# VFD_Clock.net
KiCad netlist of a schematic drawn in EasyEDA
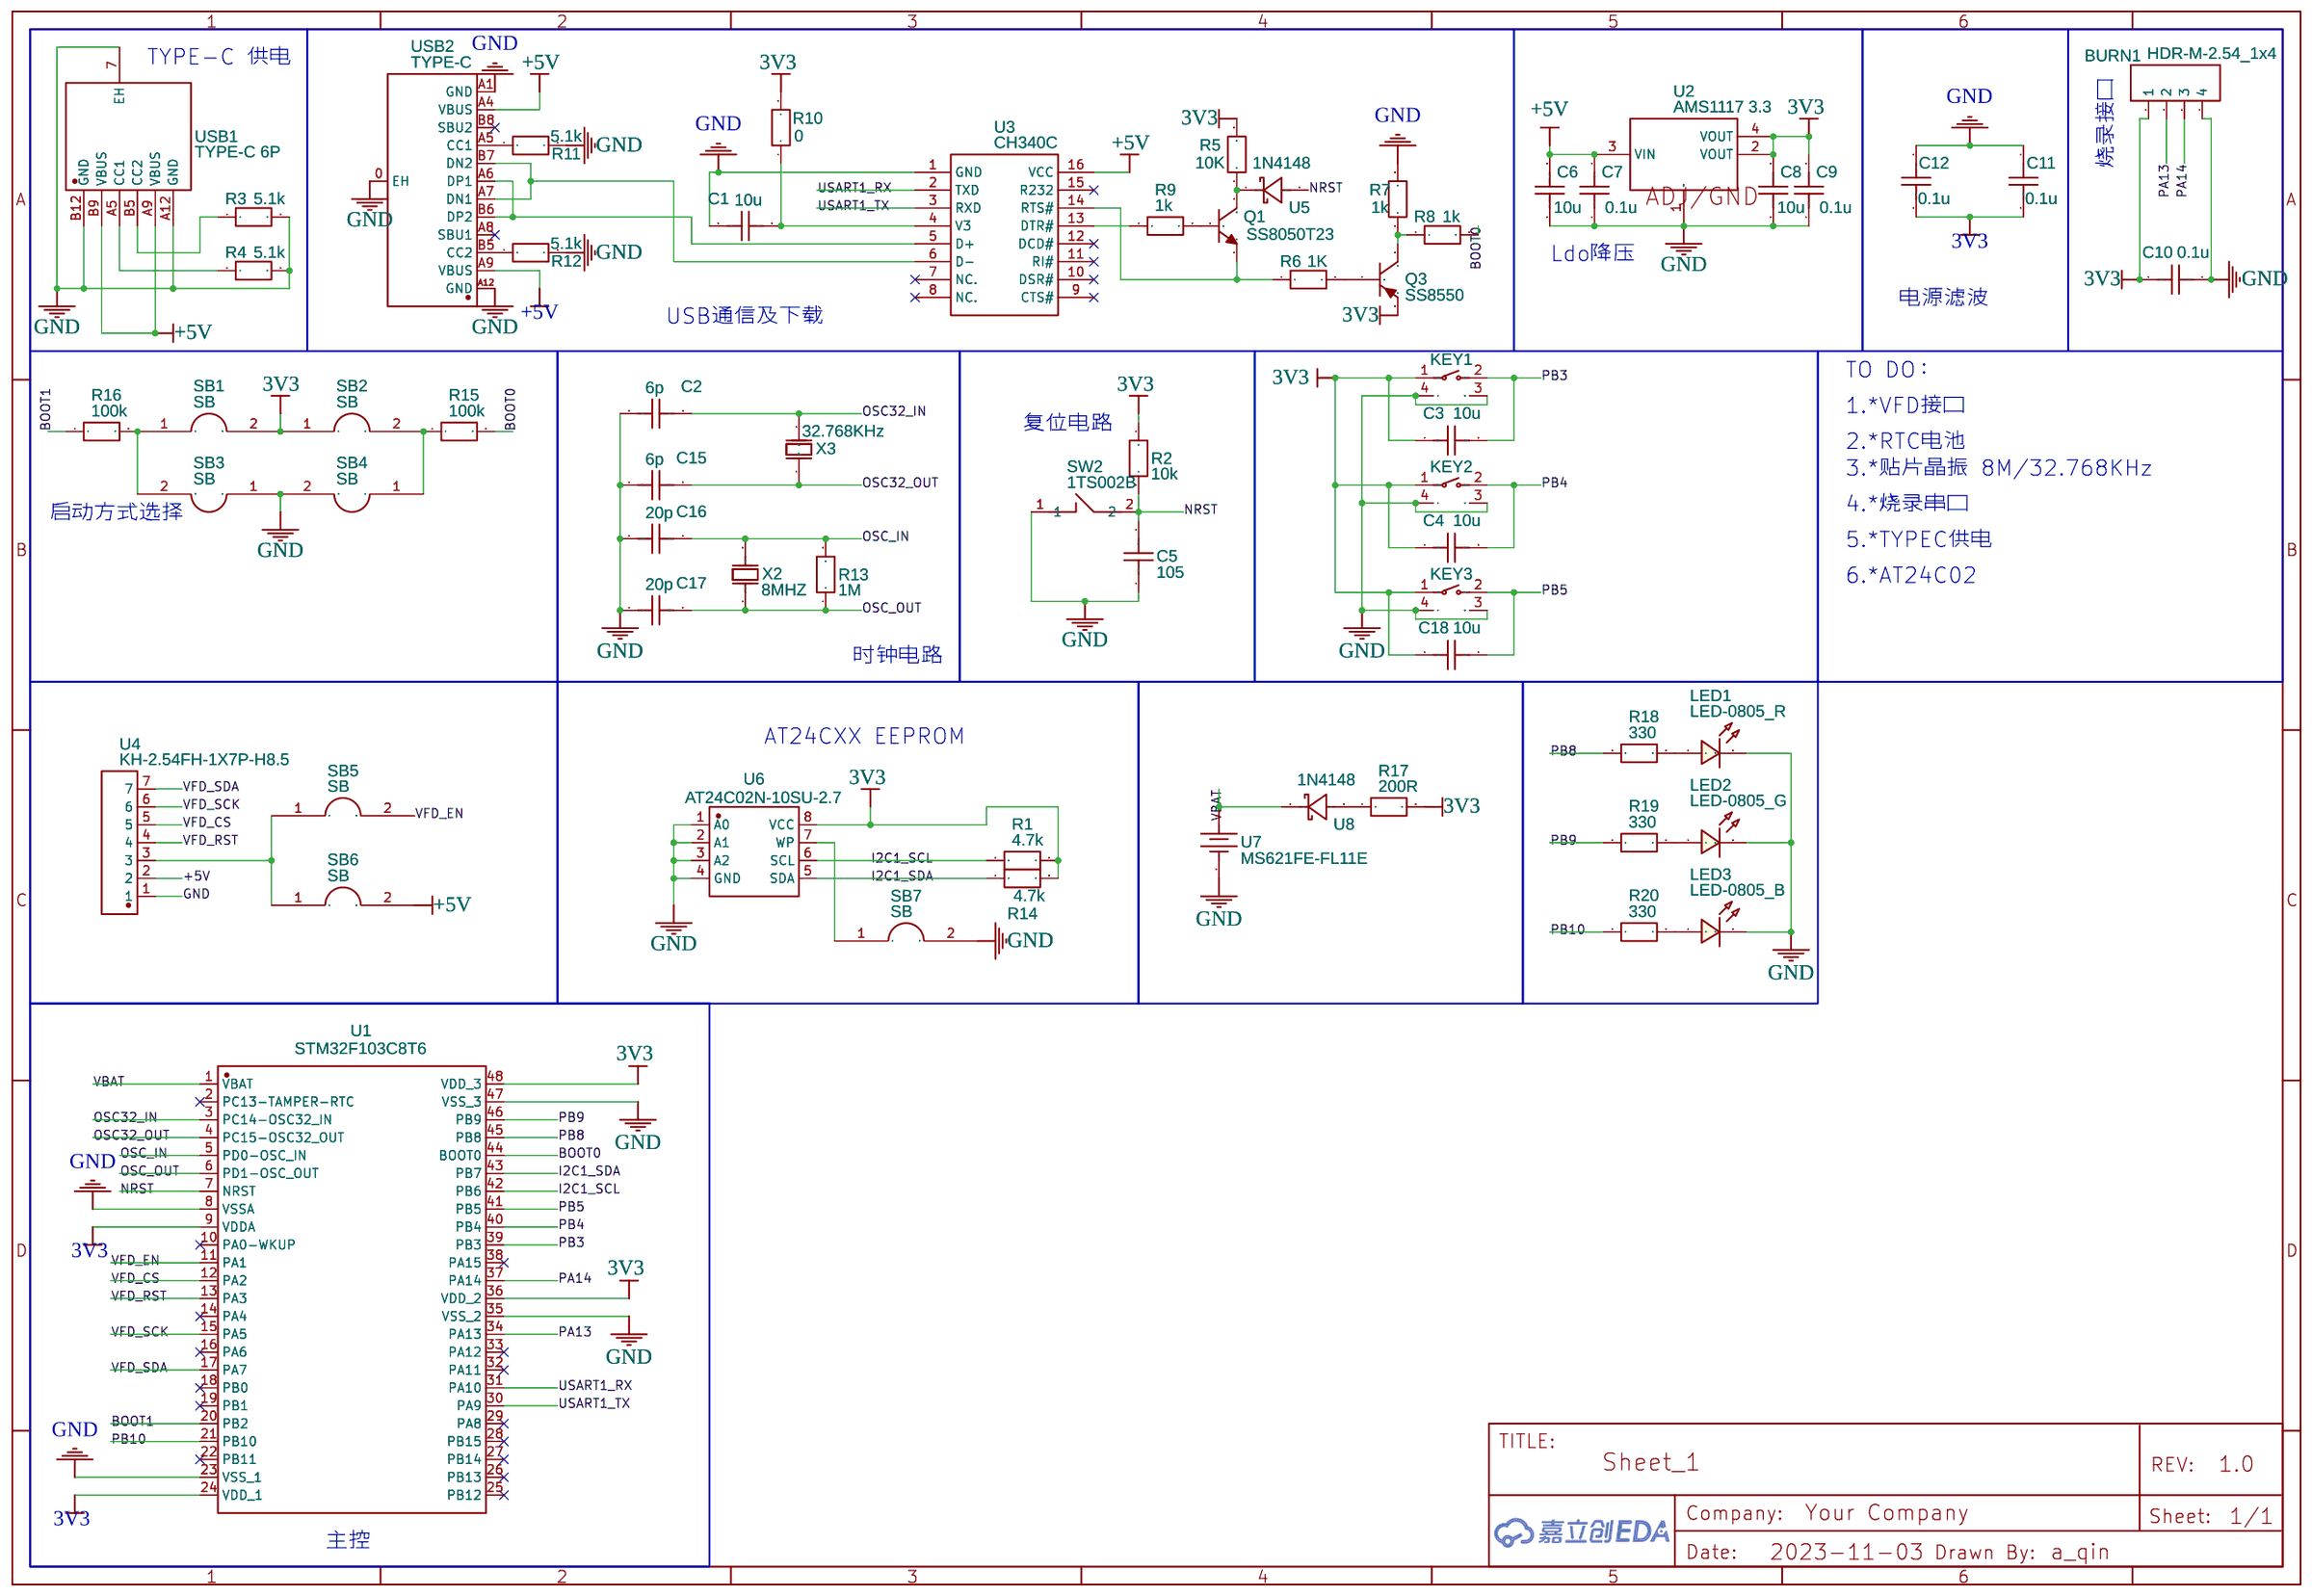
[diagram p0: schematic sheet]

(export (version "E")
  (design (tool "Eeschema 10.0.6"))
  (components
    (comp (ref "BURN1") (value "HDR-M-2.54_1x4") (libsource (lib "") (part "HDR-M-2.54_1x4")))
    (comp (ref "C1") (value "10u") (libsource (lib "") (part "C_0805_US")))
    (comp (ref "C2") (value "6p") (libsource (lib "") (part "C_0805_US")))
    (comp (ref "C3") (value "10u") (libsource (lib "") (part "C_0805_US")))
    (comp (ref "C4") (value "10u") (libsource (lib "") (part "C_0805_US")))
    (comp (ref "C5") (value "105") (libsource (lib "") (part "C_0805_US_3")))
    (comp (ref "C6") (value "10u") (libsource (lib "") (part "C_0805_US_3")))
    (comp (ref "C7") (value "0.1u") (libsource (lib "") (part "C_0805_US_3")))
    (comp (ref "C8") (value "10u") (libsource (lib "") (part "C_0805_US_3")))
    (comp (ref "C9") (value "0.1u") (libsource (lib "") (part "C_0805_US_3")))
    (comp (ref "C10") (value "0.1u") (libsource (lib "") (part "C_0805_US_2")))
    (comp (ref "C11") (value "0.1u") (libsource (lib "") (part "C_0805_US_1")))
    (comp (ref "C12") (value "0.1u") (libsource (lib "") (part "C_0805_US_1")))
    (comp (ref "C15") (value "6p") (libsource (lib "") (part "C_0805_US")))
    (comp (ref "C16") (value "20p") (libsource (lib "") (part "C_0805_US")))
    (comp (ref "C17") (value "20p") (libsource (lib "") (part "C_0805_US")))
    (comp (ref "C18") (value "10u") (libsource (lib "") (part "C_0805_US")))
    (comp (ref "KEY1")
      (value "K2-1102AQ-C4CW-01")
      (fields (field (name "Manufacturer") "韩国韩荣"))
      (libsource (lib "") (part "K2-1102AQ-C4CW-01"))
    )
    (comp (ref "KEY2")
      (value "K2-1102AQ-C4CW-01")
      (fields (field (name "Manufacturer") "韩国韩荣"))
      (libsource (lib "") (part "K2-1102AQ-C4CW-01"))
    )
    (comp (ref "KEY3")
      (value "K2-1102AQ-C4CW-01")
      (fields (field (name "Manufacturer") "韩国韩荣"))
      (libsource (lib "") (part "K2-1102AQ-C4CW-01"))
    )
    (comp (ref "LED1")
      (value "LED-0805_R")
      (fields
        (field (name "Manufacturer Part") "17-21SURC/S530-A3/TR8")
        (field (name "Manufacturer") "EVERLIGHT(台湾亿光)")
      )
      (libsource (lib "") (part "LED-0805_R"))
    )
    (comp (ref "LED2")
      (value "LED-0805_G")
      (fields (field (name "Manufacturer Part") "NCD0805G1") (field (name "Manufacturer") "国星光电"))
      (libsource (lib "") (part "LED-0805_G"))
    )
    (comp (ref "LED3")
      (value "LED-0805_B")
      (fields (field (name "Manufacturer Part") "D-B080508B1-KS2") (field (name "Manufacturer") "方舟 ARKLED"))
      (libsource (lib "") (part "LED-0805_B"))
    )
    (comp (ref "Q1")
      (value "SS8050T23")
      (fields (field (name "Manufacturer") "Me-TECH(美台高科)"))
      (libsource (lib "") (part "SS8050T23"))
    )
    (comp (ref "Q3")
      (value "SS8550")
      (fields (field (name "Manufacturer") "Yenji"))
      (libsource (lib "") (part "SS8550-C148468"))
    )
    (comp (ref "R1") (value "4.7k") (libsource (lib "") (part "R_0805_EU")))
    (comp (ref "R2") (value "10k") (libsource (lib "") (part "R_0805_EU_1")))
    (comp (ref "R3") (value "5.1k") (libsource (lib "") (part "R_0805_EU")))
    (comp (ref "R4") (value "5.1k") (libsource (lib "") (part "R_0805_EU")))
    (comp (ref "R5") (value "10K") (libsource (lib "") (part "R_0805_EU_1")))
    (comp (ref "R6") (value "1K") (libsource (lib "") (part "R_0805_EU")))
    (comp (ref "R7") (value "1k") (libsource (lib "") (part "R_0805_EU_1")))
    (comp (ref "R8") (value "1k") (libsource (lib "") (part "R_0805_EU")))
    (comp (ref "R9") (value "1k") (libsource (lib "") (part "R_0805_EU")))
    (comp (ref "R10") (value "0") (libsource (lib "") (part "R_0805_EU_1")))
    (comp (ref "R11") (value "5.1k") (libsource (lib "") (part "R_0805_EU")))
    (comp (ref "R12") (value "5.1k") (libsource (lib "") (part "R_0805_EU")))
    (comp (ref "R13") (value "1M") (libsource (lib "") (part "R_0805_EU_1")))
    (comp (ref "R14") (value "4.7k") (libsource (lib "") (part "R_0805_EU")))
    (comp (ref "R15") (value "100k") (libsource (lib "") (part "R_0805_EU")))
    (comp (ref "R16") (value "100k") (libsource (lib "") (part "R_0805_EU")))
    (comp (ref "R17") (value "200R") (libsource (lib "") (part "R_0805_EU")))
    (comp (ref "R18") (value "330") (libsource (lib "") (part "R_0805_EU")))
    (comp (ref "R19") (value "330") (libsource (lib "") (part "R_0805_EU")))
    (comp (ref "R20") (value "330") (libsource (lib "") (part "R_0805_EU")))
    (comp (ref "SB1") (value "SB") (libsource (lib "") (part "SB_1")))
    (comp (ref "SB2") (value "SB") (libsource (lib "") (part "SB_1")))
    (comp (ref "SB3") (value "SB") (libsource (lib "") (part "SB")))
    (comp (ref "SB4") (value "SB") (libsource (lib "") (part "SB")))
    (comp (ref "SB5") (value "SB") (libsource (lib "") (part "SB_1")))
    (comp (ref "SB6") (value "SB") (libsource (lib "") (part "SB_1")))
    (comp (ref "SB7") (value "SB") (libsource (lib "") (part "SB_1")))
    (comp (ref "SW2")
      (value "1TS002B")
      (fields
        (field (name "Manufacturer Part") "1TS002B-2700-5001-CT")
        (field (name "Manufacturer") "HYP(鸿源精密)")
      )
      (libsource (lib "") (part "1TS002B-2700-5001"))
    )
    (comp (ref "U1")
      (value "STM32F103C8T6")
      (fields (field (name "Manufacturer") "ST(意法半导体)"))
      (libsource (lib "") (part "STM32F103C8T6"))
    )
    (comp (ref "U2")
      (value "AMS1117 3.3")
      (fields (field (name "Manufacturer Part") "LD1117ASTR") (field (name "Manufacturer") "ST(意法半导体)"))
      (libsource (lib "") (part "LD1117ASTR"))
    )
    (comp (ref "U3")
      (value "CH340C")
      (fields (field (name "Manufacturer") "WCH(南京沁恒)"))
      (libsource (lib "") (part "CH340C"))
    )
    (comp (ref "U4")
      (value "KH-2.54FH-1X7P-H8.5")
      (fields (field (name "Manufacturer") "kinghelm(金航标)"))
      (libsource (lib "") (part "KH-2.54FH-1X7P-H8.5"))
    )
    (comp (ref "U5")
      (value "1N4148")
      (fields (field (name "Manufacturer Part") "1N4148WS-HG3-08") (field (name "Manufacturer") "VISHAY(威世)"))
      (libsource (lib "") (part "1N4148WS-HG3-08"))
    )
    (comp (ref "U6") (value "AT24C02N-10SU-2.7") (libsource (lib "") (part "AT24C02N-10SU-2.7")))
    (comp (ref "U7")
      (value "MS621FE-FL11E")
      (fields (field (name "Manufacturer") "Seiko(精工)"))
      (libsource (lib "") (part "MS621FE-FL11E"))
    )
    (comp (ref "U8")
      (value "1N4148")
      (fields (field (name "Manufacturer Part") "1N4148WS-HG3-08") (field (name "Manufacturer") "VISHAY(威世)"))
      (libsource (lib "") (part "1N4148WS-HG3-08"))
    )
    (comp (ref "USB1")
      (value "TYPE-C 6P")
      (fields (field (name "Manufacturer") "SHOU HAN(首韩)"))
      (libsource (lib "") (part "TYPE-C 6P"))
    )
    (comp (ref "USB2")
      (value "TYPE-C")
      (fields
        (field (name "Manufacturer Part") "TYPE-C 16P QTWT")
        (field (name "Manufacturer") "SHOU HAN(首韩)")
      )
      (libsource (lib "") (part "TYPE-C 16P QTWT"))
    )
    (comp (ref "X2")
      (value "8MHZ")
      (fields (field (name "Manufacturer Part") "49SAC08000182060") (field (name "Manufacturer") "JGHC"))
      (libsource (lib "") (part "49SAC08000182060"))
    )
    (comp (ref "X3")
      (value "32.768KHz")
      (fields (field (name "Manufacturer Part") "CFS-20632768EZFB") (field (name "Manufacturer") "CITIZEN"))
      (libsource (lib "") (part "CFS-20632768EZFB"))
    )
  )
  (nets
    (net (code "1") (name "+5V") (class "Default")
      (node (ref "C6") (pin "2") (pinfunction "2_2") (pintype "unspecified"))
      (node (ref "C7") (pin "2") (pinfunction "2_2") (pintype "unspecified"))
      (node (ref "SB6") (pin "2") (pinfunction "2_2") (pintype "unspecified"))
      (node (ref "U2") (pin "3") (pinfunction "VIN_3") (pintype "passive"))
      (node (ref "U3") (pin "16") (pinfunction "VCC_16") (pintype "unspecified"))
      (node (ref "U4") (pin "2") (pinfunction "2_2") (pintype "unspecified"))
      (node (ref "USB1") (pin "A9") (pinfunction "VBUS_A9") (pintype "unspecified"))
      (node (ref "USB1") (pin "B9") (pinfunction "VBUS_B9") (pintype "unspecified"))
      (node (ref "USB2") (pin "A4") (pinfunction "VBUS_A4") (pintype "unspecified"))
      (node (ref "USB2") (pin "A9") (pinfunction "VBUS_A9") (pintype "unspecified"))
    )
    (net (code "2") (name "/BOOT0") (class "Default")
      (node (ref "R15") (pin "2") (pinfunction "2_2") (pintype "unspecified"))
      (node (ref "R8") (pin "2") (pinfunction "2_2") (pintype "unspecified"))
      (node (ref "U1") (pin "44") (pinfunction "BOOT0_44") (pintype "unspecified"))
    )
    (net (code "3") (name "/BOOT1") (class "Default")
      (node (ref "R16") (pin "1") (pinfunction "1_1") (pintype "unspecified"))
      (node (ref "U1") (pin "20") (pinfunction "PB2_20") (pintype "unspecified"))
    )
    (net (code "4") (name "/I2C1_SCL") (class "Default")
      (node (ref "R1") (pin "1") (pinfunction "1_1") (pintype "unspecified"))
      (node (ref "U1") (pin "42") (pinfunction "PB6_42") (pintype "unspecified"))
      (node (ref "U6") (pin "6") (pinfunction "SCL_6") (pintype "unspecified"))
    )
    (net (code "5") (name "/I2C1_SDA") (class "Default")
      (node (ref "R14") (pin "1") (pinfunction "1_1") (pintype "unspecified"))
      (node (ref "U1") (pin "43") (pinfunction "PB7_43") (pintype "unspecified"))
      (node (ref "U6") (pin "5") (pinfunction "SDA_5") (pintype "unspecified"))
    )
    (net (code "6") (name "/NRST") (class "Default")
      (node (ref "C5") (pin "2") (pinfunction "2_2") (pintype "unspecified"))
      (node (ref "R2") (pin "1") (pinfunction "1_1") (pintype "unspecified"))
      (node (ref "SW2") (pin "2") (pinfunction "2_2") (pintype "unspecified"))
      (node (ref "U1") (pin "7") (pinfunction "NRST_7") (pintype "unspecified"))
      (node (ref "U5") (pin "2") (pinfunction "A_2") (pintype "unspecified"))
    )
    (net (code "7") (name "/OSC32_IN") (class "Default")
      (node (ref "C2") (pin "2") (pinfunction "2_2") (pintype "unspecified"))
      (node (ref "U1") (pin "3") (pinfunction "PC14-OSC32_IN_3") (pintype "unspecified"))
      (node (ref "X3") (pin "2") (pinfunction "OSC2_2") (pintype "input"))
    )
    (net (code "8") (name "/OSC32_OUT") (class "Default")
      (node (ref "C15") (pin "2") (pinfunction "2_2") (pintype "unspecified"))
      (node (ref "U1") (pin "4") (pinfunction "PC15-OSC32_OUT_4") (pintype "unspecified"))
      (node (ref "X3") (pin "1") (pinfunction "OSC1_1") (pintype "input"))
    )
    (net (code "9") (name "/OSC_IN") (class "Default")
      (node (ref "C16") (pin "2") (pinfunction "2_2") (pintype "unspecified"))
      (node (ref "R13") (pin "2") (pinfunction "2_2") (pintype "unspecified"))
      (node (ref "U1") (pin "5") (pinfunction "PD0-OSC_IN_5") (pintype "unspecified"))
      (node (ref "X2") (pin "2") (pinfunction "OSC2_2") (pintype "input"))
    )
    (net (code "10") (name "/OSC_OUT") (class "Default")
      (node (ref "C17") (pin "2") (pinfunction "2_2") (pintype "unspecified"))
      (node (ref "R13") (pin "1") (pinfunction "1_1") (pintype "unspecified"))
      (node (ref "U1") (pin "6") (pinfunction "PD1-OSC_OUT_6") (pintype "unspecified"))
      (node (ref "X2") (pin "1") (pinfunction "OSC1_1") (pintype "input"))
    )
    (net (code "11") (name "/PA13") (class "Default")
      (node (ref "BURN1") (pin "2") (pinfunction "2_2") (pintype "unspecified"))
      (node (ref "U1") (pin "34") (pinfunction "PA13_34") (pintype "unspecified"))
    )
    (net (code "12") (name "/PA14") (class "Default")
      (node (ref "BURN1") (pin "3") (pinfunction "3_3") (pintype "unspecified"))
      (node (ref "U1") (pin "37") (pinfunction "PA14_37") (pintype "unspecified"))
    )
    (net (code "13") (name "/PB3") (class "Default")
      (node (ref "C3") (pin "2") (pinfunction "2_2") (pintype "unspecified"))
      (node (ref "KEY1") (pin "2") (pinfunction "2_2") (pintype "unspecified"))
      (node (ref "U1") (pin "39") (pinfunction "PB3_39") (pintype "unspecified"))
    )
    (net (code "14") (name "/PB4") (class "Default")
      (node (ref "C4") (pin "2") (pinfunction "2_2") (pintype "unspecified"))
      (node (ref "KEY2") (pin "2") (pinfunction "2_2") (pintype "unspecified"))
      (node (ref "U1") (pin "40") (pinfunction "PB4_40") (pintype "unspecified"))
    )
    (net (code "15") (name "/PB5") (class "Default")
      (node (ref "C18") (pin "2") (pinfunction "2_2") (pintype "unspecified"))
      (node (ref "KEY3") (pin "2") (pinfunction "2_2") (pintype "unspecified"))
      (node (ref "U1") (pin "41") (pinfunction "PB5_41") (pintype "unspecified"))
    )
    (net (code "16") (name "/PB8") (class "Default")
      (node (ref "R18") (pin "1") (pinfunction "1_1") (pintype "unspecified"))
      (node (ref "U1") (pin "45") (pinfunction "PB8_45") (pintype "unspecified"))
    )
    (net (code "17") (name "/PB9") (class "Default")
      (node (ref "R19") (pin "1") (pinfunction "1_1") (pintype "unspecified"))
      (node (ref "U1") (pin "46") (pinfunction "PB9_46") (pintype "unspecified"))
    )
    (net (code "18") (name "/PB10") (class "Default")
      (node (ref "R20") (pin "1") (pinfunction "1_1") (pintype "unspecified"))
      (node (ref "U1") (pin "21") (pinfunction "PB10_21") (pintype "unspecified"))
    )
    (net (code "19") (name "/USART1_RX") (class "Default")
      (node (ref "U1") (pin "31") (pinfunction "PA10_31") (pintype "unspecified"))
      (node (ref "U3") (pin "2") (pinfunction "TXD_2") (pintype "unspecified"))
    )
    (net (code "20") (name "/USART1_TX") (class "Default")
      (node (ref "U1") (pin "30") (pinfunction "PA9_30") (pintype "unspecified"))
      (node (ref "U3") (pin "3") (pinfunction "RXD_3") (pintype "unspecified"))
    )
    (net (code "21") (name "/VBAT") (class "Default")
      (node (ref "U1") (pin "1") (pinfunction "VBAT_1") (pintype "unspecified"))
      (node (ref "U7") (pin "1") (pinfunction "+_1") (pintype "passive"))
      (node (ref "U8") (pin "1") (pinfunction "K_1") (pintype "unspecified"))
    )
    (net (code "22") (name "/VFD_CS") (class "Default")
      (node (ref "U1") (pin "12") (pinfunction "PA2_12") (pintype "unspecified"))
      (node (ref "U4") (pin "5") (pinfunction "5_5") (pintype "unspecified"))
    )
    (net (code "23") (name "/VFD_EN") (class "Default")
      (node (ref "SB5") (pin "2") (pinfunction "2_2") (pintype "unspecified"))
      (node (ref "U1") (pin "11") (pinfunction "PA1_11") (pintype "unspecified"))
    )
    (net (code "24") (name "/VFD_RST") (class "Default")
      (node (ref "U1") (pin "13") (pinfunction "PA3_13") (pintype "unspecified"))
      (node (ref "U4") (pin "4") (pinfunction "4_4") (pintype "unspecified"))
    )
    (net (code "25") (name "/VFD_SCK") (class "Default")
      (node (ref "U1") (pin "15") (pinfunction "PA5_15") (pintype "unspecified"))
      (node (ref "U4") (pin "6") (pinfunction "6_6") (pintype "unspecified"))
    )
    (net (code "26") (name "/VFD_SDA") (class "Default")
      (node (ref "U1") (pin "17") (pinfunction "PA7_17") (pintype "unspecified"))
      (node (ref "U4") (pin "7") (pinfunction "7_7") (pintype "unspecified"))
    )
    (net (code "27") (name "3V3") (class "Default")
      (node (ref "BURN1") (pin "1") (pinfunction "1_1") (pintype "unspecified"))
      (node (ref "C10") (pin "2") (pinfunction "2_2") (pintype "unspecified"))
      (node (ref "C11") (pin "2") (pinfunction "2_2") (pintype "unspecified"))
      (node (ref "C12") (pin "2") (pinfunction "2_2") (pintype "unspecified"))
      (node (ref "C18") (pin "1") (pinfunction "1_1") (pintype "unspecified"))
      (node (ref "C3") (pin "1") (pinfunction "1_1") (pintype "unspecified"))
      (node (ref "C4") (pin "1") (pinfunction "1_1") (pintype "unspecified"))
      (node (ref "C8") (pin "2") (pinfunction "2_2") (pintype "unspecified"))
      (node (ref "C9") (pin "2") (pinfunction "2_2") (pintype "unspecified"))
      (node (ref "KEY1") (pin "1") (pinfunction "1_1") (pintype "unspecified"))
      (node (ref "KEY2") (pin "1") (pinfunction "1_1") (pintype "unspecified"))
      (node (ref "KEY3") (pin "1") (pinfunction "1_1") (pintype "unspecified"))
      (node (ref "Q3") (pin "2") (pinfunction "E_2") (pintype "unspecified"))
      (node (ref "R1") (pin "2") (pinfunction "2_2") (pintype "unspecified"))
      (node (ref "R10") (pin "2") (pinfunction "2_2") (pintype "unspecified"))
      (node (ref "R14") (pin "2") (pinfunction "2_2") (pintype "unspecified"))
      (node (ref "R17") (pin "2") (pinfunction "2_2") (pintype "unspecified"))
      (node (ref "R2") (pin "2") (pinfunction "2_2") (pintype "unspecified"))
      (node (ref "R5") (pin "2") (pinfunction "2_2") (pintype "unspecified"))
      (node (ref "SB1") (pin "2") (pinfunction "2_2") (pintype "unspecified"))
      (node (ref "SB2") (pin "1") (pinfunction "1_1") (pintype "unspecified"))
      (node (ref "U1") (pin "24") (pinfunction "VDD_1_24") (pintype "unspecified"))
      (node (ref "U1") (pin "36") (pinfunction "VDD_2_36") (pintype "unspecified"))
      (node (ref "U1") (pin "48") (pinfunction "VDD_3_48") (pintype "unspecified"))
      (node (ref "U1") (pin "9") (pinfunction "VDDA_9") (pintype "unspecified"))
      (node (ref "U2") (pin "2") (pinfunction "VOUT_2") (pintype "passive"))
      (node (ref "U2") (pin "4") (pinfunction "VOUT_4") (pintype "passive"))
      (node (ref "U6") (pin "8") (pinfunction "VCC_8") (pintype "unspecified"))
    )
    (net (code "28") (name "GND") (class "Default")
      (node (ref "BURN1") (pin "4") (pinfunction "4_4") (pintype "unspecified"))
      (node (ref "C1") (pin "1") (pinfunction "1_1") (pintype "unspecified"))
      (node (ref "C10") (pin "1") (pinfunction "1_1") (pintype "unspecified"))
      (node (ref "C11") (pin "1") (pinfunction "1_1") (pintype "unspecified"))
      (node (ref "C12") (pin "1") (pinfunction "1_1") (pintype "unspecified"))
      (node (ref "C15") (pin "1") (pinfunction "1_1") (pintype "unspecified"))
      (node (ref "C16") (pin "1") (pinfunction "1_1") (pintype "unspecified"))
      (node (ref "C17") (pin "1") (pinfunction "1_1") (pintype "unspecified"))
      (node (ref "C2") (pin "1") (pinfunction "1_1") (pintype "unspecified"))
      (node (ref "C5") (pin "1") (pinfunction "1_1") (pintype "unspecified"))
      (node (ref "C6") (pin "1") (pinfunction "1_1") (pintype "unspecified"))
      (node (ref "C7") (pin "1") (pinfunction "1_1") (pintype "unspecified"))
      (node (ref "C8") (pin "1") (pinfunction "1_1") (pintype "unspecified"))
      (node (ref "C9") (pin "1") (pinfunction "1_1") (pintype "unspecified"))
      (node (ref "KEY1") (pin "3") (pinfunction "3_3") (pintype "unspecified"))
      (node (ref "KEY1") (pin "4") (pinfunction "4_4") (pintype "unspecified"))
      (node (ref "KEY2") (pin "3") (pinfunction "3_3") (pintype "unspecified"))
      (node (ref "KEY2") (pin "4") (pinfunction "4_4") (pintype "unspecified"))
      (node (ref "KEY3") (pin "3") (pinfunction "3_3") (pintype "unspecified"))
      (node (ref "KEY3") (pin "4") (pinfunction "4_4") (pintype "unspecified"))
      (node (ref "LED1") (pin "2") (pinfunction "2_2") (pintype "unspecified"))
      (node (ref "LED2") (pin "2") (pinfunction "2_2") (pintype "unspecified"))
      (node (ref "LED3") (pin "2") (pinfunction "2_2") (pintype "unspecified"))
      (node (ref "R11") (pin "2") (pinfunction "2_2") (pintype "unspecified"))
      (node (ref "R12") (pin "2") (pinfunction "2_2") (pintype "unspecified"))
      (node (ref "R3") (pin "2") (pinfunction "2_2") (pintype "unspecified"))
      (node (ref "R4") (pin "2") (pinfunction "2_2") (pintype "unspecified"))
      (node (ref "R7") (pin "2") (pinfunction "2_2") (pintype "unspecified"))
      (node (ref "SB3") (pin "1") (pinfunction "1_1") (pintype "unspecified"))
      (node (ref "SB4") (pin "2") (pinfunction "2_2") (pintype "unspecified"))
      (node (ref "SB7") (pin "2") (pinfunction "2_2") (pintype "unspecified"))
      (node (ref "SW2") (pin "1") (pinfunction "1_1") (pintype "unspecified"))
      (node (ref "U1") (pin "23") (pinfunction "VSS_1_23") (pintype "unspecified"))
      (node (ref "U1") (pin "35") (pinfunction "VSS_2_35") (pintype "unspecified"))
      (node (ref "U1") (pin "47") (pinfunction "VSS_3_47") (pintype "unspecified"))
      (node (ref "U1") (pin "8") (pinfunction "VSSA_8") (pintype "unspecified"))
      (node (ref "U2") (pin "1") (pinfunction "ADJ/GND_1") (pintype "passive"))
      (node (ref "U3") (pin "1") (pinfunction "GND_1") (pintype "unspecified"))
      (node (ref "U4") (pin "1") (pinfunction "1_1") (pintype "unspecified"))
      (node (ref "U6") (pin "1") (pinfunction "A0_1") (pintype "unspecified"))
      (node (ref "U6") (pin "2") (pinfunction "A1_2") (pintype "unspecified"))
      (node (ref "U6") (pin "3") (pinfunction "A2_3") (pintype "unspecified"))
      (node (ref "U6") (pin "4") (pinfunction "GND_4") (pintype "unspecified"))
      (node (ref "U7") (pin "2") (pinfunction "-_2") (pintype "passive"))
      (node (ref "USB1") (pin "7") (pinfunction "EH_7") (pintype "unspecified"))
      (node (ref "USB1") (pin "A12") (pinfunction "GND_A12") (pintype "unspecified"))
      (node (ref "USB1") (pin "B12") (pinfunction "GND_B12") (pintype "unspecified"))
      (node (ref "USB2") (pin "0") (pinfunction "EH_0") (pintype "unspecified"))
      (node (ref "USB2") (pin "A1") (pinfunction "GND_A1") (pintype "unspecified"))
      (node (ref "USB2") (pin "A12") (pinfunction "GND_A12") (pintype "unspecified"))
    )
    (net (code "29") (name "Net-(LED1-Pad1)") (class "Default")
      (node (ref "LED1") (pin "1") (pinfunction "1_1") (pintype "unspecified"))
      (node (ref "R18") (pin "2") (pinfunction "2_2") (pintype "unspecified"))
    )
    (net (code "30") (name "Net-(LED2-Pad1)") (class "Default")
      (node (ref "LED2") (pin "1") (pinfunction "1_1") (pintype "unspecified"))
      (node (ref "R19") (pin "2") (pinfunction "2_2") (pintype "unspecified"))
    )
    (net (code "31") (name "Net-(LED3-Pad1)") (class "Default")
      (node (ref "LED3") (pin "1") (pinfunction "1_1") (pintype "unspecified"))
      (node (ref "R20") (pin "2") (pinfunction "2_2") (pintype "unspecified"))
    )
    (net (code "32") (name "Net-(Q1-B)") (class "Default")
      (node (ref "Q1") (pin "1") (pinfunction "B_1") (pintype "input"))
      (node (ref "R9") (pin "2") (pinfunction "2_2") (pintype "unspecified"))
    )
    (net (code "33") (name "Net-(Q1-C)") (class "Default")
      (node (ref "Q1") (pin "3") (pinfunction "C_3") (pintype "input"))
      (node (ref "R5") (pin "1") (pinfunction "1_1") (pintype "unspecified"))
      (node (ref "U5") (pin "1") (pinfunction "K_1") (pintype "unspecified"))
    )
    (net (code "34") (name "Net-(Q1-E)") (class "Default")
      (node (ref "Q1") (pin "2") (pinfunction "E_2") (pintype "input"))
      (node (ref "R6") (pin "1") (pinfunction "1_1") (pintype "unspecified"))
      (node (ref "U3") (pin "14") (pinfunction "RTS#_14") (pintype "unspecified"))
    )
    (net (code "35") (name "Net-(Q3-B)") (class "Default")
      (node (ref "Q3") (pin "1") (pinfunction "B_1") (pintype "unspecified"))
      (node (ref "R6") (pin "2") (pinfunction "2_2") (pintype "unspecified"))
    )
    (net (code "36") (name "Net-(Q3-C)") (class "Default")
      (node (ref "Q3") (pin "3") (pinfunction "C_3") (pintype "unspecified"))
      (node (ref "R7") (pin "1") (pinfunction "1_1") (pintype "unspecified"))
      (node (ref "R8") (pin "1") (pinfunction "1_1") (pintype "unspecified"))
    )
    (net (code "37") (name "Net-(R15-Pad1)") (class "Default")
      (node (ref "R15") (pin "1") (pinfunction "1_1") (pintype "unspecified"))
      (node (ref "SB2") (pin "2") (pinfunction "2_2") (pintype "unspecified"))
      (node (ref "SB4") (pin "1") (pinfunction "1_1") (pintype "unspecified"))
    )
    (net (code "38") (name "Net-(R16-Pad2)") (class "Default")
      (node (ref "R16") (pin "2") (pinfunction "2_2") (pintype "unspecified"))
      (node (ref "SB1") (pin "1") (pinfunction "1_1") (pintype "unspecified"))
      (node (ref "SB3") (pin "2") (pinfunction "2_2") (pintype "unspecified"))
    )
    (net (code "39") (name "Net-(SB5-Pad1)") (class "Default")
      (node (ref "SB5") (pin "1") (pinfunction "1_1") (pintype "unspecified"))
      (node (ref "SB6") (pin "1") (pinfunction "1_1") (pintype "unspecified"))
      (node (ref "U4") (pin "3") (pinfunction "3_3") (pintype "unspecified"))
    )
    (net (code "40") (name "Net-(U3-D+)") (class "Default")
      (node (ref "U3") (pin "5") (pinfunction "D+_5") (pintype "unspecified"))
      (node (ref "USB2") (pin "A6") (pinfunction "DP1_A6") (pintype "unspecified"))
      (node (ref "USB2") (pin "B6") (pinfunction "DP2_B6") (pintype "unspecified"))
    )
    (net (code "41") (name "Net-(U3-D-)") (class "Default")
      (node (ref "U3") (pin "6") (pinfunction "D-_6") (pintype "unspecified"))
      (node (ref "USB2") (pin "A7") (pinfunction "DN1_A7") (pintype "unspecified"))
      (node (ref "USB2") (pin "B7") (pinfunction "DN2_B7") (pintype "unspecified"))
    )
    (net (code "42") (name "Net-(U3-DTR#)") (class "Default")
      (node (ref "R9") (pin "1") (pinfunction "1_1") (pintype "unspecified"))
      (node (ref "U3") (pin "13") (pinfunction "DTR#_13") (pintype "unspecified"))
    )
    (net (code "43") (name "Net-(U3-V3)") (class "Default")
      (node (ref "C1") (pin "2") (pinfunction "2_2") (pintype "unspecified"))
      (node (ref "R10") (pin "1") (pinfunction "1_1") (pintype "unspecified"))
      (node (ref "U3") (pin "4") (pinfunction "V3_4") (pintype "unspecified"))
    )
    (net (code "44") (name "Net-(U6-WP)") (class "Default")
      (node (ref "SB7") (pin "1") (pinfunction "1_1") (pintype "unspecified"))
      (node (ref "U6") (pin "7") (pinfunction "WP_7") (pintype "unspecified"))
    )
    (net (code "45") (name "Net-(U8-A)") (class "Default")
      (node (ref "R17") (pin "1") (pinfunction "1_1") (pintype "unspecified"))
      (node (ref "U8") (pin "2") (pinfunction "A_2") (pintype "unspecified"))
    )
    (net (code "46") (name "Net-(USB1-CC1)") (class "Default")
      (node (ref "R4") (pin "1") (pinfunction "1_1") (pintype "unspecified"))
      (node (ref "USB1") (pin "A5") (pinfunction "CC1_A5") (pintype "unspecified"))
    )
    (net (code "47") (name "Net-(USB1-CC2)") (class "Default")
      (node (ref "R3") (pin "1") (pinfunction "1_1") (pintype "unspecified"))
      (node (ref "USB1") (pin "B5") (pinfunction "CC2_B5") (pintype "unspecified"))
    )
    (net (code "48") (name "Net-(USB2-CC1)") (class "Default")
      (node (ref "R11") (pin "1") (pinfunction "1_1") (pintype "unspecified"))
      (node (ref "USB2") (pin "A5") (pinfunction "CC1_A5") (pintype "unspecified"))
    )
    (net (code "49") (name "Net-(USB2-CC2)") (class "Default")
      (node (ref "R12") (pin "1") (pinfunction "1_1") (pintype "unspecified"))
      (node (ref "USB2") (pin "B5") (pinfunction "CC2_B5") (pintype "unspecified"))
    )
    (net (code "50") (name "unconnected-(U1-PA0-WKUP-Pad10)") (class "Default")
      (node (ref "U1") (pin "10") (pinfunction "PA0-WKUP_10") (pintype "unspecified+no_connect"))
    )
    (net (code "51") (name "unconnected-(U1-PA4-Pad14)") (class "Default")
      (node (ref "U1") (pin "14") (pinfunction "PA4_14") (pintype "unspecified+no_connect"))
    )
    (net (code "52") (name "unconnected-(U1-PA6-Pad16)") (class "Default")
      (node (ref "U1") (pin "16") (pinfunction "PA6_16") (pintype "unspecified+no_connect"))
    )
    (net (code "53") (name "unconnected-(U1-PA8-Pad29)") (class "Default")
      (node (ref "U1") (pin "29") (pinfunction "PA8_29") (pintype "unspecified+no_connect"))
    )
    (net (code "54") (name "unconnected-(U1-PA11-Pad32)") (class "Default")
      (node (ref "U1") (pin "32") (pinfunction "PA11_32") (pintype "unspecified+no_connect"))
    )
    (net (code "55") (name "unconnected-(U1-PA12-Pad33)") (class "Default")
      (node (ref "U1") (pin "33") (pinfunction "PA12_33") (pintype "unspecified+no_connect"))
    )
    (net (code "56") (name "unconnected-(U1-PA15-Pad38)") (class "Default")
      (node (ref "U1") (pin "38") (pinfunction "PA15_38") (pintype "unspecified+no_connect"))
    )
    (net (code "57") (name "unconnected-(U1-PB0-Pad18)") (class "Default")
      (node (ref "U1") (pin "18") (pinfunction "PB0_18") (pintype "unspecified+no_connect"))
    )
    (net (code "58") (name "unconnected-(U1-PB1-Pad19)") (class "Default")
      (node (ref "U1") (pin "19") (pinfunction "PB1_19") (pintype "unspecified+no_connect"))
    )
    (net (code "59") (name "unconnected-(U1-PB11-Pad22)") (class "Default")
      (node (ref "U1") (pin "22") (pinfunction "PB11_22") (pintype "unspecified+no_connect"))
    )
    (net (code "60") (name "unconnected-(U1-PB12-Pad25)") (class "Default")
      (node (ref "U1") (pin "25") (pinfunction "PB12_25") (pintype "unspecified+no_connect"))
    )
    (net (code "61") (name "unconnected-(U1-PB13-Pad26)") (class "Default")
      (node (ref "U1") (pin "26") (pinfunction "PB13_26") (pintype "unspecified+no_connect"))
    )
    (net (code "62") (name "unconnected-(U1-PB14-Pad27)") (class "Default")
      (node (ref "U1") (pin "27") (pinfunction "PB14_27") (pintype "unspecified+no_connect"))
    )
    (net (code "63") (name "unconnected-(U1-PB15-Pad28)") (class "Default")
      (node (ref "U1") (pin "28") (pinfunction "PB15_28") (pintype "unspecified+no_connect"))
    )
    (net (code "64") (name "unconnected-(U1-PC13-TAMPER-RTC-Pad2)") (class "Default")
      (node (ref "U1") (pin "2") (pinfunction "PC13-TAMPER-RTC_2") (pintype "unspecified+no_connect"))
    )
    (net (code "65") (name "unconnected-(U3-CTS#-Pad9)") (class "Default")
      (node (ref "U3") (pin "9") (pinfunction "CTS#_9") (pintype "unspecified+no_connect"))
    )
    (net (code "66") (name "unconnected-(U3-DCD#-Pad12)") (class "Default")
      (node (ref "U3") (pin "12") (pinfunction "DCD#_12") (pintype "unspecified+no_connect"))
    )
    (net (code "67") (name "unconnected-(U3-DSR#-Pad10)") (class "Default")
      (node (ref "U3") (pin "10") (pinfunction "DSR#_10") (pintype "unspecified+no_connect"))
    )
    (net (code "68") (name "unconnected-(U3-NC.-Pad7)") (class "Default")
      (node (ref "U3") (pin "7") (pinfunction "NC._7") (pintype "unspecified+no_connect"))
    )
    (net (code "69") (name "unconnected-(U3-NC.-Pad8)") (class "Default")
      (node (ref "U3") (pin "8") (pinfunction "NC._8") (pintype "unspecified+no_connect"))
    )
    (net (code "70") (name "unconnected-(U3-R232-Pad15)") (class "Default")
      (node (ref "U3") (pin "15") (pinfunction "R232_15") (pintype "unspecified+no_connect"))
    )
    (net (code "71") (name "unconnected-(U3-RI#-Pad11)") (class "Default")
      (node (ref "U3") (pin "11") (pinfunction "RI#_11") (pintype "unspecified+no_connect"))
    )
    (net (code "72") (name "unconnected-(USB2-SBU1-PadA8)") (class "Default")
      (node (ref "USB2") (pin "A8") (pinfunction "SBU1_A8") (pintype "unspecified+no_connect"))
    )
    (net (code "73") (name "unconnected-(USB2-SBU2-PadB8)") (class "Default")
      (node (ref "USB2") (pin "B8") (pinfunction "SBU2_B8") (pintype "unspecified+no_connect"))
    )
  )
)
